# input-selector.net
KiCad netlist of a schematic drawn in EAGLE
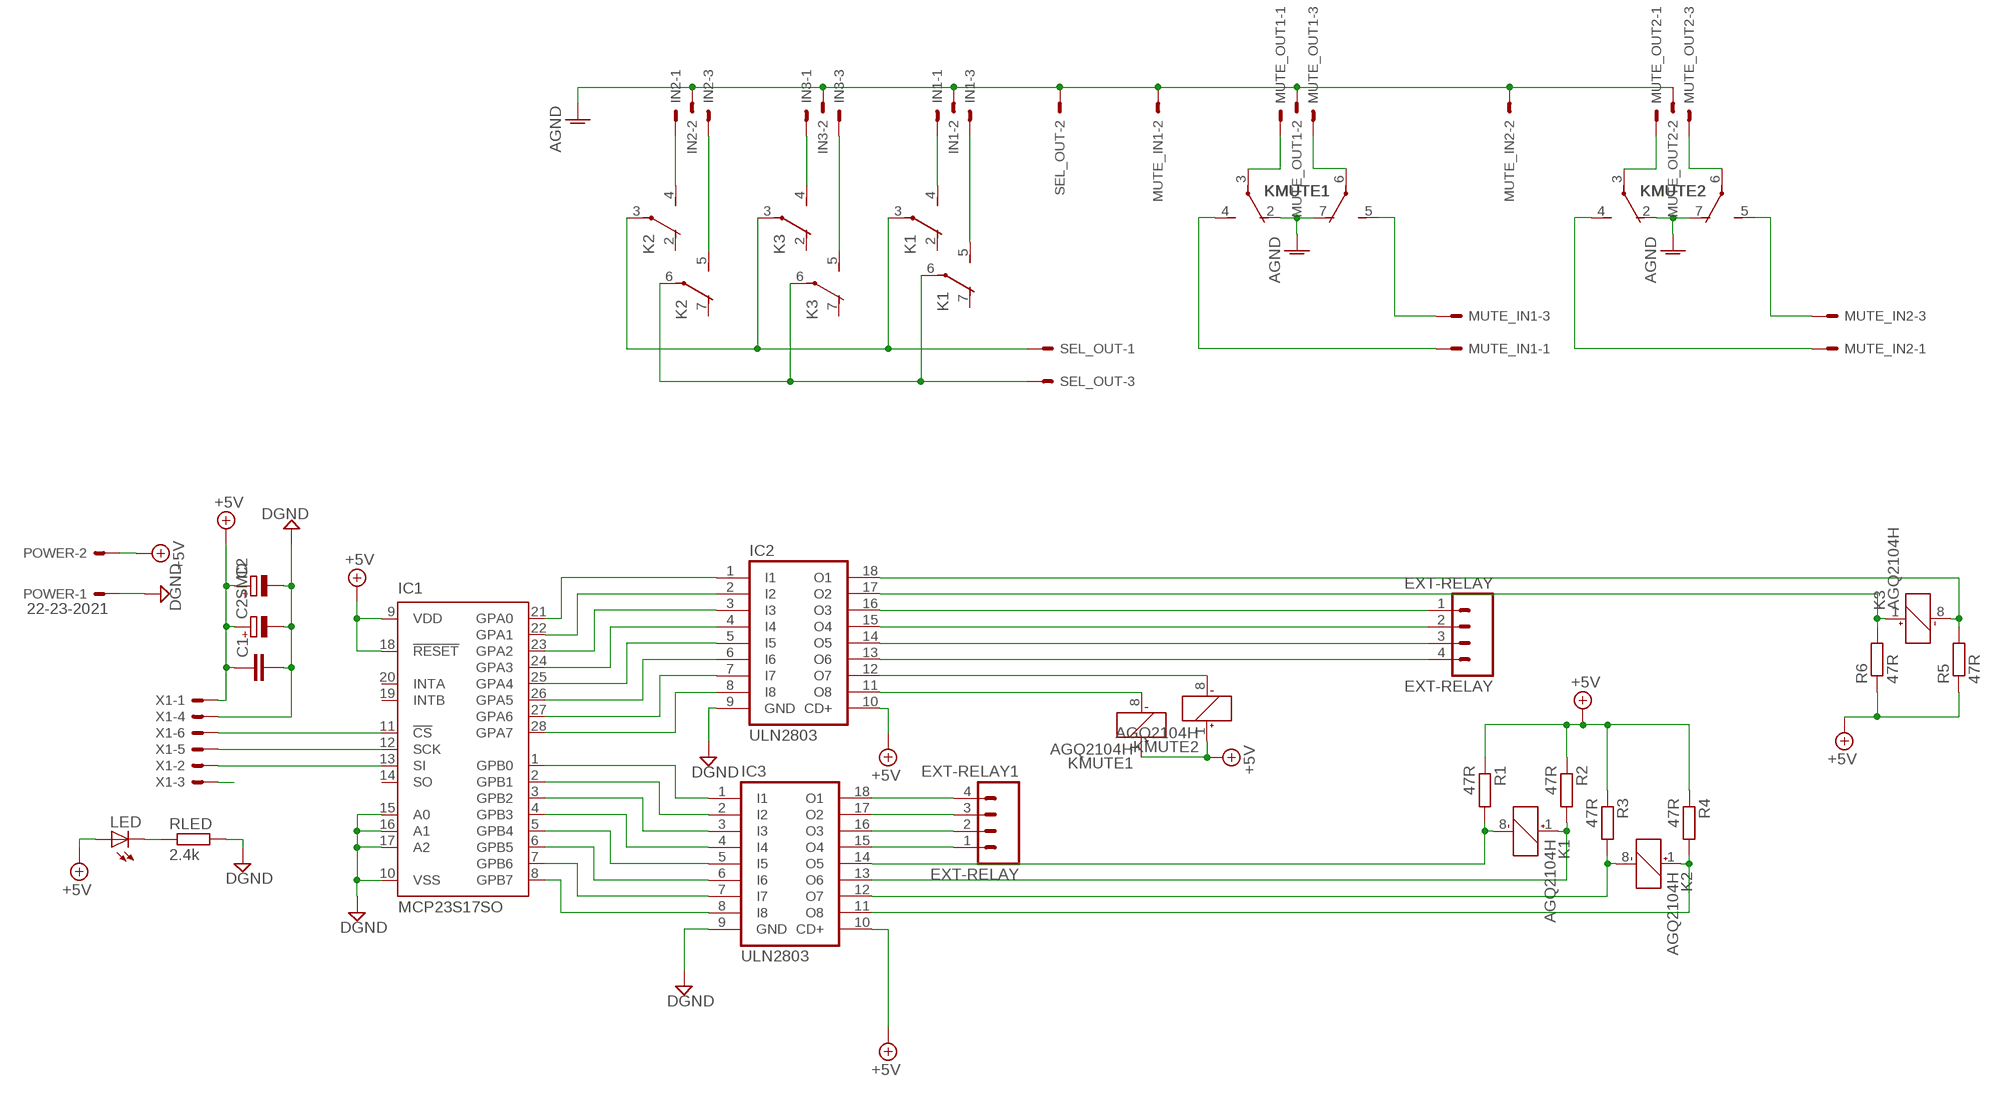
[diagram p0: schematic, sheet 1]

(export (version "E")
  (design (tool "Eeschema 10.0.6"))
  (components
    (comp (ref "C1")
      (value "C-EUC1206")
      (footprint "eagle-import:C1206")
      (libsource (lib "eagle-import") (part "C-EUC1206"))
    )
    (comp (ref "C2")
      (value "CPOL-EUE3.5-8")
      (footprint "eagle-import:E3,5-8")
      (libsource (lib "eagle-import") (part "CPOL-EUE3.5-8"))
    )
    (comp (ref "C2SMD")
      (value "CPOL-EUE")
      (footprint "eagle-import:PANASONIC_E")
      (libsource (lib "eagle-import") (part "CPOL-EUE"))
    )
    (comp (ref "EXT-RELAY")
      (value "EXT-RELAY")
      (footprint "eagle-import:MOLEX-1X4")
      (libsource (lib "eagle-import") (part "M04POLAR"))
    )
    (comp (ref "EXT-RELAY1")
      (value "EXT-RELAY")
      (footprint "eagle-import:MOLEX-1X4")
      (libsource (lib "eagle-import") (part "M04POLAR"))
    )
    (comp (ref "IC1")
      (value "MCP23S17SO")
      (footprint "eagle-import:SO28W")
      (fields (field (name "MF") "MICROCHIP") (field (name "MPN") "MCP23S17-E/SO"))
      (libsource (lib "eagle-import") (part "MCP23S17SO"))
    )
    (comp (ref "IC2")
      (value "ULN2803")
      (footprint "eagle-import:SO-18W")
      (libsource (lib "eagle-import") (part "ULN2803ADW"))
    )
    (comp (ref "IC3")
      (value "ULN2803")
      (footprint "eagle-import:SO-18W")
      (libsource (lib "eagle-import") (part "ULN2803ADW"))
    )
    (comp (ref "IN1")
      (value "22-23-2031")
      (footprint "eagle-import:22-23-2031")
      (fields (field (name "MF") "MOLEX"))
      (libsource (lib "eagle-import") (part "22-23-2031"))
    )
    (comp (ref "IN2")
      (value "22-23-2031")
      (footprint "eagle-import:22-23-2031")
      (fields (field (name "MF") "MOLEX"))
      (libsource (lib "eagle-import") (part "22-23-2031"))
    )
    (comp (ref "IN3")
      (value "22-23-2031")
      (footprint "eagle-import:22-23-2031")
      (fields (field (name "MF") "MOLEX"))
      (libsource (lib "eagle-import") (part "22-23-2031"))
    )
    (comp (ref "K1")
      (value "AGQ2104H")
      (footprint "eagle-import:PCBBOARD")
      (libsource (lib "eagle-import") (part "AGQ2104H"))
    )
    (comp (ref "K2")
      (value "AGQ2104H")
      (footprint "eagle-import:PCBBOARD")
      (libsource (lib "eagle-import") (part "AGQ2104H"))
    )
    (comp (ref "K3")
      (value "AGQ2104H")
      (footprint "eagle-import:PCBBOARD")
      (libsource (lib "eagle-import") (part "AGQ2104H"))
    )
    (comp (ref "KMUTE1")
      (value "AGQ2104H")
      (footprint "eagle-import:PCBBOARD")
      (libsource (lib "eagle-import") (part "AGQ2104H"))
    )
    (comp (ref "KMUTE2")
      (value "AGQ2104H")
      (footprint "eagle-import:PCBBOARD")
      (libsource (lib "eagle-import") (part "AGQ2104H"))
    )
    (comp (ref "LED")
      (value "LEDSMT1206")
      (footprint "eagle-import:1206")
      (libsource (lib "eagle-import") (part "LEDSMT1206"))
    )
    (comp (ref "MUTE_IN1")
      (value "22-23-2031")
      (footprint "eagle-import:22-23-2031")
      (fields (field (name "MF") "MOLEX"))
      (libsource (lib "eagle-import") (part "22-23-2031"))
    )
    (comp (ref "MUTE_IN2")
      (value "22-23-2031")
      (footprint "eagle-import:22-23-2031")
      (fields (field (name "MF") "MOLEX"))
      (libsource (lib "eagle-import") (part "22-23-2031"))
    )
    (comp (ref "MUTE_OUT1")
      (value "22-23-2031")
      (footprint "eagle-import:22-23-2031")
      (fields (field (name "MF") "MOLEX"))
      (libsource (lib "eagle-import") (part "22-23-2031"))
    )
    (comp (ref "MUTE_OUT2")
      (value "22-23-2031")
      (footprint "eagle-import:22-23-2031")
      (fields (field (name "MF") "MOLEX"))
      (libsource (lib "eagle-import") (part "22-23-2031"))
    )
    (comp (ref "POWER")
      (value "22-23-2021")
      (footprint "eagle-import:22-23-2021")
      (fields (field (name "MF") "MOLEX"))
      (libsource (lib "eagle-import") (part "22-23-2021"))
    )
    (comp (ref "R1")
      (value "47R")
      (footprint "eagle-import:R1206")
      (libsource (lib "eagle-import") (part "R-EU_R1206"))
    )
    (comp (ref "R2")
      (value "47R")
      (footprint "eagle-import:R1206")
      (libsource (lib "eagle-import") (part "R-EU_R1206"))
    )
    (comp (ref "R3")
      (value "47R")
      (footprint "eagle-import:R1206")
      (libsource (lib "eagle-import") (part "R-EU_R1206"))
    )
    (comp (ref "R4")
      (value "47R")
      (footprint "eagle-import:R1206")
      (libsource (lib "eagle-import") (part "R-EU_R1206"))
    )
    (comp (ref "R5")
      (value "47R")
      (footprint "eagle-import:R1206")
      (libsource (lib "eagle-import") (part "R-EU_R1206"))
    )
    (comp (ref "R6")
      (value "47R")
      (footprint "eagle-import:R1206")
      (libsource (lib "eagle-import") (part "R-EU_R1206"))
    )
    (comp (ref "RLED")
      (value "2.4k")
      (footprint "eagle-import:R1206")
      (libsource (lib "eagle-import") (part "R-EU_R1206"))
    )
    (comp (ref "SEL_OUT")
      (value "22-23-2031")
      (footprint "eagle-import:22-23-2031")
      (fields (field (name "MF") "MOLEX"))
      (libsource (lib "eagle-import") (part "22-23-2031"))
    )
    (comp (ref "X1")
      (value "22-23-2061")
      (footprint "eagle-import:22-23-2061")
      (fields (field (name "MF") "MOLEX"))
      (libsource (lib "eagle-import") (part "22-23-2061"))
    )
  )
  (nets
    (net (code "1") (name "+5V") (class "Default")
      (node (ref "C1") (pin "1") (pinfunction "1_1") (pintype "passive"))
      (node (ref "C2") (pin "+") (pinfunction "+_+") (pintype "passive"))
      (node (ref "C2SMD") (pin "+") (pinfunction "+_+") (pintype "passive"))
      (node (ref "IC1") (pin "18") (pinfunction "~{RESET}_18") (pintype "input"))
      (node (ref "IC1") (pin "9") (pinfunction "VDD_9") (pintype "power_in"))
      (node (ref "IC2") (pin "10") (pinfunction "CD+_10") (pintype "passive"))
      (node (ref "IC3") (pin "10") (pinfunction "CD+_10") (pintype "passive"))
      (node (ref "KMUTE1") (pin "1") (pinfunction "+_1") (pintype "passive"))
      (node (ref "KMUTE2") (pin "1") (pinfunction "+_1") (pintype "passive"))
      (node (ref "LED") (pin "A") (pinfunction "A_A") (pintype "passive"))
      (node (ref "POWER") (pin "2") (pinfunction "S_2") (pintype "passive"))
      (node (ref "R1") (pin "1") (pinfunction "1_1") (pintype "passive"))
      (node (ref "R2") (pin "1") (pinfunction "1_1") (pintype "passive"))
      (node (ref "R3") (pin "1") (pinfunction "1_1") (pintype "passive"))
      (node (ref "R4") (pin "1") (pinfunction "1_1") (pintype "passive"))
      (node (ref "R5") (pin "1") (pinfunction "1_1") (pintype "passive"))
      (node (ref "R6") (pin "1") (pinfunction "1_1") (pintype "passive"))
      (node (ref "X1") (pin "1") (pinfunction "S_1") (pintype "passive"))
    )
    (net (code "2") (name "AGND") (class "Default")
      (node (ref "IN1") (pin "2") (pinfunction "S_2") (pintype "passive"))
      (node (ref "IN2") (pin "2") (pinfunction "S_2") (pintype "passive"))
      (node (ref "IN3") (pin "2") (pinfunction "S_2") (pintype "passive"))
      (node (ref "KMUTE1") (pin "2") (pinfunction "O_2") (pintype "passive"))
      (node (ref "KMUTE1") (pin "7") (pinfunction "O_7") (pintype "passive"))
      (node (ref "KMUTE2") (pin "2") (pinfunction "O_2") (pintype "passive"))
      (node (ref "KMUTE2") (pin "7") (pinfunction "O_7") (pintype "passive"))
      (node (ref "MUTE_IN1") (pin "2") (pinfunction "S_2") (pintype "passive"))
      (node (ref "MUTE_IN2") (pin "2") (pinfunction "S_2") (pintype "passive"))
      (node (ref "MUTE_OUT1") (pin "2") (pinfunction "S_2") (pintype "passive"))
      (node (ref "MUTE_OUT2") (pin "2") (pinfunction "S_2") (pintype "passive"))
      (node (ref "SEL_OUT") (pin "2") (pinfunction "S_2") (pintype "passive"))
    )
    (net (code "3") (name "DGND") (class "Default")
      (node (ref "C1") (pin "2") (pinfunction "2_2") (pintype "passive"))
      (node (ref "C2") (pin "-") (pinfunction "-_-") (pintype "passive"))
      (node (ref "C2SMD") (pin "-") (pinfunction "-_-") (pintype "passive"))
      (node (ref "IC1") (pin "10") (pinfunction "VSS_10") (pintype "power_in"))
      (node (ref "IC1") (pin "15") (pinfunction "A0_15") (pintype "input"))
      (node (ref "IC1") (pin "16") (pinfunction "A1_16") (pintype "input"))
      (node (ref "IC1") (pin "17") (pinfunction "A2_17") (pintype "input"))
      (node (ref "IC2") (pin "9") (pinfunction "GND_9") (pintype "power_in"))
      (node (ref "IC3") (pin "9") (pinfunction "GND_9") (pintype "power_in"))
      (node (ref "POWER") (pin "1") (pinfunction "S_1") (pintype "passive"))
      (node (ref "RLED") (pin "2") (pinfunction "2_2") (pintype "passive"))
      (node (ref "X1") (pin "4") (pinfunction "S_4") (pintype "passive"))
    )
    (net (code "4") (name "Net-(IC1-GPA0)") (class "Default")
      (node (ref "IC1") (pin "21") (pinfunction "GPA0_21") (pintype "bidirectional"))
      (node (ref "IC2") (pin "1") (pinfunction "I1_1") (pintype "input"))
    )
    (net (code "5") (name "Net-(IC1-GPA1)") (class "Default")
      (node (ref "IC1") (pin "22") (pinfunction "GPA1_22") (pintype "bidirectional"))
      (node (ref "IC2") (pin "2") (pinfunction "I2_2") (pintype "input"))
    )
    (net (code "6") (name "Net-(IC1-GPA2)") (class "Default")
      (node (ref "IC1") (pin "23") (pinfunction "GPA2_23") (pintype "bidirectional"))
      (node (ref "IC2") (pin "3") (pinfunction "I3_3") (pintype "input"))
    )
    (net (code "7") (name "Net-(IC1-GPA3)") (class "Default")
      (node (ref "IC1") (pin "24") (pinfunction "GPA3_24") (pintype "bidirectional"))
      (node (ref "IC2") (pin "4") (pinfunction "I4_4") (pintype "input"))
    )
    (net (code "8") (name "Net-(IC1-GPA4)") (class "Default")
      (node (ref "IC1") (pin "25") (pinfunction "GPA4_25") (pintype "bidirectional"))
      (node (ref "IC2") (pin "5") (pinfunction "I5_5") (pintype "input"))
    )
    (net (code "9") (name "Net-(IC1-GPA5)") (class "Default")
      (node (ref "IC1") (pin "26") (pinfunction "GPA5_26") (pintype "bidirectional"))
      (node (ref "IC2") (pin "6") (pinfunction "I6_6") (pintype "input"))
    )
    (net (code "10") (name "Net-(IC1-GPA6)") (class "Default")
      (node (ref "IC1") (pin "27") (pinfunction "GPA6_27") (pintype "bidirectional"))
      (node (ref "IC2") (pin "7") (pinfunction "I7_7") (pintype "input"))
    )
    (net (code "11") (name "Net-(IC1-GPA7)") (class "Default")
      (node (ref "IC1") (pin "28") (pinfunction "GPA7_28") (pintype "bidirectional"))
      (node (ref "IC2") (pin "8") (pinfunction "I8_8") (pintype "input"))
    )
    (net (code "12") (name "Net-(IC1-GPB0)") (class "Default")
      (node (ref "IC1") (pin "1") (pinfunction "GPB0_1") (pintype "bidirectional"))
      (node (ref "IC3") (pin "1") (pinfunction "I1_1") (pintype "input"))
    )
    (net (code "13") (name "Net-(IC1-GPB1)") (class "Default")
      (node (ref "IC1") (pin "2") (pinfunction "GPB1_2") (pintype "bidirectional"))
      (node (ref "IC3") (pin "2") (pinfunction "I2_2") (pintype "input"))
    )
    (net (code "14") (name "Net-(IC1-GPB2)") (class "Default")
      (node (ref "IC1") (pin "3") (pinfunction "GPB2_3") (pintype "bidirectional"))
      (node (ref "IC3") (pin "3") (pinfunction "I3_3") (pintype "input"))
    )
    (net (code "15") (name "Net-(IC1-GPB3)") (class "Default")
      (node (ref "IC1") (pin "4") (pinfunction "GPB3_4") (pintype "bidirectional"))
      (node (ref "IC3") (pin "4") (pinfunction "I4_4") (pintype "input"))
    )
    (net (code "16") (name "Net-(IC1-GPB4)") (class "Default")
      (node (ref "IC1") (pin "5") (pinfunction "GPB4_5") (pintype "bidirectional"))
      (node (ref "IC3") (pin "5") (pinfunction "I5_5") (pintype "input"))
    )
    (net (code "17") (name "Net-(IC1-GPB5)") (class "Default")
      (node (ref "IC1") (pin "6") (pinfunction "GPB5_6") (pintype "bidirectional"))
      (node (ref "IC3") (pin "6") (pinfunction "I6_6") (pintype "input"))
    )
    (net (code "18") (name "Net-(IC1-GPB6)") (class "Default")
      (node (ref "IC1") (pin "7") (pinfunction "GPB6_7") (pintype "bidirectional"))
      (node (ref "IC3") (pin "7") (pinfunction "I7_7") (pintype "input"))
    )
    (net (code "19") (name "Net-(IC1-GPB7)") (class "Default")
      (node (ref "IC1") (pin "8") (pinfunction "GPB7_8") (pintype "bidirectional"))
      (node (ref "IC3") (pin "8") (pinfunction "I8_8") (pintype "input"))
    )
    (net (code "20") (name "Net-(IC1-SCK)") (class "Default")
      (node (ref "IC1") (pin "12") (pinfunction "SCK_12") (pintype "input"))
      (node (ref "X1") (pin "5") (pinfunction "S_5") (pintype "passive"))
    )
    (net (code "21") (name "Net-(IC1-SI)") (class "Default")
      (node (ref "IC1") (pin "13") (pinfunction "SI_13") (pintype "input"))
      (node (ref "X1") (pin "2") (pinfunction "S_2") (pintype "passive"))
    )
    (net (code "22") (name "Net-(IC1-~{CS})") (class "Default")
      (node (ref "IC1") (pin "11") (pinfunction "~{CS}_11") (pintype "input"))
      (node (ref "X1") (pin "6") (pinfunction "S_6") (pintype "passive"))
    )
    (net (code "23") (name "Net-(IC2-O1)") (class "Default")
      (node (ref "IC2") (pin "18") (pinfunction "O1_18") (pintype "open_collector"))
      (node (ref "K3") (pin "8") (pinfunction "-_8") (pintype "passive"))
      (node (ref "R5") (pin "2") (pinfunction "2_2") (pintype "passive"))
    )
    (net (code "24") (name "Net-(IC2-O2)") (class "Default")
      (node (ref "IC2") (pin "17") (pinfunction "O2_17") (pintype "open_collector"))
      (node (ref "K3") (pin "1") (pinfunction "+_1") (pintype "passive"))
      (node (ref "R6") (pin "2") (pinfunction "2_2") (pintype "passive"))
    )
    (net (code "25") (name "Net-(IC2-O3)") (class "Default")
      (node (ref "EXT-RELAY") (pin "1") (pinfunction "1_1") (pintype "passive"))
      (node (ref "IC2") (pin "16") (pinfunction "O3_16") (pintype "open_collector"))
    )
    (net (code "26") (name "Net-(IC2-O4)") (class "Default")
      (node (ref "EXT-RELAY") (pin "2") (pinfunction "2_2") (pintype "passive"))
      (node (ref "IC2") (pin "15") (pinfunction "O4_15") (pintype "open_collector"))
    )
    (net (code "27") (name "Net-(IC2-O5)") (class "Default")
      (node (ref "EXT-RELAY") (pin "3") (pinfunction "3_3") (pintype "passive"))
      (node (ref "IC2") (pin "14") (pinfunction "O5_14") (pintype "open_collector"))
    )
    (net (code "28") (name "Net-(IC2-O6)") (class "Default")
      (node (ref "EXT-RELAY") (pin "4") (pinfunction "4_4") (pintype "passive"))
      (node (ref "IC2") (pin "13") (pinfunction "O6_13") (pintype "open_collector"))
    )
    (net (code "29") (name "Net-(IC2-O7)") (class "Default")
      (node (ref "IC2") (pin "12") (pinfunction "O7_12") (pintype "open_collector"))
      (node (ref "KMUTE2") (pin "8") (pinfunction "-_8") (pintype "passive"))
    )
    (net (code "30") (name "Net-(IC2-O8)") (class "Default")
      (node (ref "IC2") (pin "11") (pinfunction "O8_11") (pintype "open_collector"))
      (node (ref "KMUTE1") (pin "8") (pinfunction "-_8") (pintype "passive"))
    )
    (net (code "31") (name "Net-(IC3-O1)") (class "Default")
      (node (ref "EXT-RELAY1") (pin "4") (pinfunction "4_4") (pintype "passive"))
      (node (ref "IC3") (pin "18") (pinfunction "O1_18") (pintype "open_collector"))
    )
    (net (code "32") (name "Net-(IC3-O2)") (class "Default")
      (node (ref "EXT-RELAY1") (pin "3") (pinfunction "3_3") (pintype "passive"))
      (node (ref "IC3") (pin "17") (pinfunction "O2_17") (pintype "open_collector"))
    )
    (net (code "33") (name "Net-(IC3-O3)") (class "Default")
      (node (ref "EXT-RELAY1") (pin "2") (pinfunction "2_2") (pintype "passive"))
      (node (ref "IC3") (pin "16") (pinfunction "O3_16") (pintype "open_collector"))
    )
    (net (code "34") (name "Net-(IC3-O4)") (class "Default")
      (node (ref "EXT-RELAY1") (pin "1") (pinfunction "1_1") (pintype "passive"))
      (node (ref "IC3") (pin "15") (pinfunction "O4_15") (pintype "open_collector"))
    )
    (net (code "35") (name "Net-(IC3-O5)") (class "Default")
      (node (ref "IC3") (pin "14") (pinfunction "O5_14") (pintype "open_collector"))
      (node (ref "K1") (pin "8") (pinfunction "-_8") (pintype "passive"))
      (node (ref "R1") (pin "2") (pinfunction "2_2") (pintype "passive"))
    )
    (net (code "36") (name "Net-(IC3-O6)") (class "Default")
      (node (ref "IC3") (pin "13") (pinfunction "O6_13") (pintype "open_collector"))
      (node (ref "K1") (pin "1") (pinfunction "+_1") (pintype "passive"))
      (node (ref "R2") (pin "2") (pinfunction "2_2") (pintype "passive"))
    )
    (net (code "37") (name "Net-(IC3-O7)") (class "Default")
      (node (ref "IC3") (pin "12") (pinfunction "O7_12") (pintype "open_collector"))
      (node (ref "K2") (pin "8") (pinfunction "-_8") (pintype "passive"))
      (node (ref "R3") (pin "2") (pinfunction "2_2") (pintype "passive"))
    )
    (net (code "38") (name "Net-(IC3-O8)") (class "Default")
      (node (ref "IC3") (pin "11") (pinfunction "O8_11") (pintype "open_collector"))
      (node (ref "K2") (pin "1") (pinfunction "+_1") (pintype "passive"))
      (node (ref "R4") (pin "2") (pinfunction "2_2") (pintype "passive"))
    )
    (net (code "39") (name "Net-(IN1A-S)") (class "Default")
      (node (ref "IN1") (pin "1") (pinfunction "S_1") (pintype "passive"))
      (node (ref "K1") (pin "4") (pinfunction "S_4") (pintype "passive"))
    )
    (net (code "40") (name "Net-(IN1C-S)") (class "Default")
      (node (ref "IN1") (pin "3") (pinfunction "S_3") (pintype "passive"))
      (node (ref "K1") (pin "5") (pinfunction "S_5") (pintype "passive"))
    )
    (net (code "41") (name "Net-(IN2A-S)") (class "Default")
      (node (ref "IN2") (pin "1") (pinfunction "S_1") (pintype "passive"))
      (node (ref "K2") (pin "4") (pinfunction "S_4") (pintype "passive"))
    )
    (net (code "42") (name "Net-(IN2C-S)") (class "Default")
      (node (ref "IN2") (pin "3") (pinfunction "S_3") (pintype "passive"))
      (node (ref "K2") (pin "5") (pinfunction "S_5") (pintype "passive"))
    )
    (net (code "43") (name "Net-(IN3A-S)") (class "Default")
      (node (ref "IN3") (pin "1") (pinfunction "S_1") (pintype "passive"))
      (node (ref "K3") (pin "4") (pinfunction "S_4") (pintype "passive"))
    )
    (net (code "44") (name "Net-(IN3C-S)") (class "Default")
      (node (ref "IN3") (pin "3") (pinfunction "S_3") (pintype "passive"))
      (node (ref "K3") (pin "5") (pinfunction "S_5") (pintype "passive"))
    )
    (net (code "45") (name "Net-(K1B-P)") (class "Default")
      (node (ref "K1") (pin "6") (pinfunction "P_6") (pintype "passive"))
      (node (ref "K2") (pin "6") (pinfunction "P_6") (pintype "passive"))
      (node (ref "K3") (pin "6") (pinfunction "P_6") (pintype "passive"))
      (node (ref "SEL_OUT") (pin "3") (pinfunction "S_3") (pintype "passive"))
    )
    (net (code "46") (name "Net-(K1C-P)") (class "Default")
      (node (ref "K1") (pin "3") (pinfunction "P_3") (pintype "passive"))
      (node (ref "K2") (pin "3") (pinfunction "P_3") (pintype "passive"))
      (node (ref "K3") (pin "3") (pinfunction "P_3") (pintype "passive"))
      (node (ref "SEL_OUT") (pin "1") (pinfunction "S_1") (pintype "passive"))
    )
    (net (code "47") (name "Net-(KMUTE1B-P)") (class "Default")
      (node (ref "KMUTE1") (pin "6") (pinfunction "P_6") (pintype "passive"))
      (node (ref "MUTE_OUT1") (pin "3") (pinfunction "S_3") (pintype "passive"))
    )
    (net (code "48") (name "Net-(KMUTE1B-S)") (class "Default")
      (node (ref "KMUTE1") (pin "5") (pinfunction "S_5") (pintype "passive"))
      (node (ref "MUTE_IN1") (pin "3") (pinfunction "S_3") (pintype "passive"))
    )
    (net (code "49") (name "Net-(KMUTE1C-P)") (class "Default")
      (node (ref "KMUTE1") (pin "3") (pinfunction "P_3") (pintype "passive"))
      (node (ref "MUTE_OUT1") (pin "1") (pinfunction "S_1") (pintype "passive"))
    )
    (net (code "50") (name "Net-(KMUTE1C-S)") (class "Default")
      (node (ref "KMUTE1") (pin "4") (pinfunction "S_4") (pintype "passive"))
      (node (ref "MUTE_IN1") (pin "1") (pinfunction "S_1") (pintype "passive"))
    )
    (net (code "51") (name "Net-(KMUTE2B-P)") (class "Default")
      (node (ref "KMUTE2") (pin "6") (pinfunction "P_6") (pintype "passive"))
      (node (ref "MUTE_OUT2") (pin "3") (pinfunction "S_3") (pintype "passive"))
    )
    (net (code "52") (name "Net-(KMUTE2B-S)") (class "Default")
      (node (ref "KMUTE2") (pin "5") (pinfunction "S_5") (pintype "passive"))
      (node (ref "MUTE_IN2") (pin "3") (pinfunction "S_3") (pintype "passive"))
    )
    (net (code "53") (name "Net-(KMUTE2C-P)") (class "Default")
      (node (ref "KMUTE2") (pin "3") (pinfunction "P_3") (pintype "passive"))
      (node (ref "MUTE_OUT2") (pin "1") (pinfunction "S_1") (pintype "passive"))
    )
    (net (code "54") (name "Net-(KMUTE2C-S)") (class "Default")
      (node (ref "KMUTE2") (pin "4") (pinfunction "S_4") (pintype "passive"))
      (node (ref "MUTE_IN2") (pin "1") (pinfunction "S_1") (pintype "passive"))
    )
    (net (code "55") (name "Net-(LED-PadC)") (class "Default")
      (node (ref "LED") (pin "C") (pinfunction "C_C") (pintype "passive"))
      (node (ref "RLED") (pin "1") (pinfunction "1_1") (pintype "passive"))
    )
    (net (code "56") (name "unconnected-(IC1-INTA-Pad20)") (class "Default")
      (node (ref "IC1") (pin "20") (pinfunction "INTA_20") (pintype "output"))
    )
    (net (code "57") (name "unconnected-(IC1-INTB-Pad19)") (class "Default")
      (node (ref "IC1") (pin "19") (pinfunction "INTB_19") (pintype "output"))
    )
    (net (code "58") (name "unconnected-(IC1-SO-Pad14)") (class "Default")
      (node (ref "IC1") (pin "14") (pinfunction "SO_14") (pintype "output"))
    )
    (net (code "59") (name "unconnected-(K1B-O-Pad7)") (class "Default")
      (node (ref "K1") (pin "7") (pinfunction "O_7") (pintype "passive"))
    )
    (net (code "60") (name "unconnected-(K1C-O-Pad2)") (class "Default")
      (node (ref "K1") (pin "2") (pinfunction "O_2") (pintype "passive"))
    )
    (net (code "61") (name "unconnected-(K2B-O-Pad7)") (class "Default")
      (node (ref "K2") (pin "7") (pinfunction "O_7") (pintype "passive"))
    )
    (net (code "62") (name "unconnected-(K2C-O-Pad2)") (class "Default")
      (node (ref "K2") (pin "2") (pinfunction "O_2") (pintype "passive"))
    )
    (net (code "63") (name "unconnected-(K3B-O-Pad7)") (class "Default")
      (node (ref "K3") (pin "7") (pinfunction "O_7") (pintype "passive"))
    )
    (net (code "64") (name "unconnected-(K3C-O-Pad2)") (class "Default")
      (node (ref "K3") (pin "2") (pinfunction "O_2") (pintype "passive"))
    )
    (net (code "65") (name "unconnected-(X1C-S-Pad3)") (class "Default")
      (node (ref "X1") (pin "3") (pinfunction "S_3") (pintype "passive"))
    )
  )
)
